# Boost-Shield-V1.net
KiCad netlist of a schematic drawn in Altium Designer
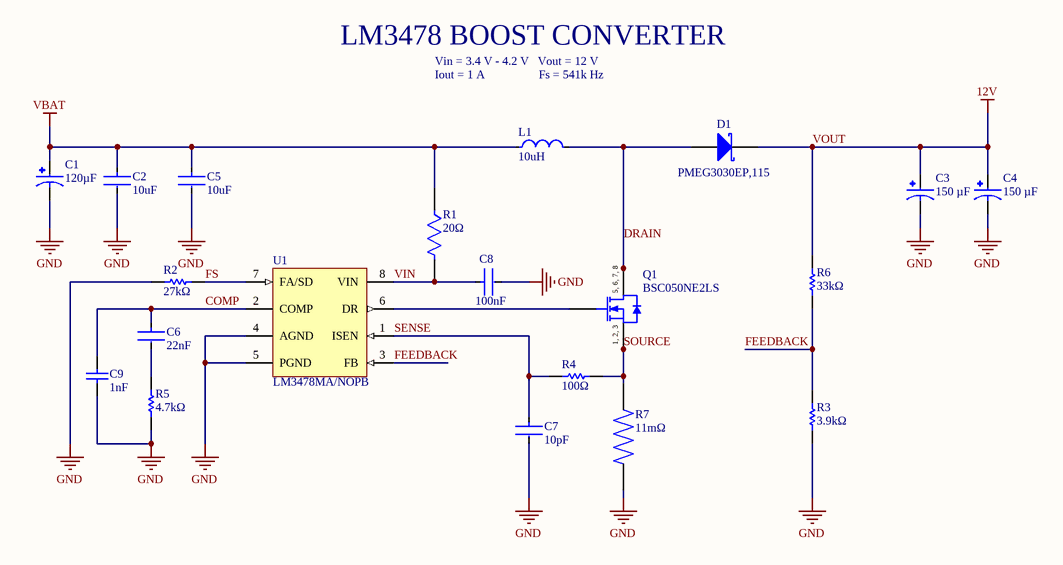
[diagram p0: Boost-Shield-V1.SchDoc]

(export (version "E")
  (design (tool "Eeschema 10.0.6"))
  (components
    (comp (ref "C1")
      (value "120µF")
      (footprint "CAP_EEFCX0J121R")
      (description "120µF 6.3V Aluminum - Polymer Capacitors 2917 (7343 Metric) 15mOhm 2000 Hrs @ 105°C  EEFCX0J121R")
      (libsource (lib "Boost-Shield") (part "EEFCX0J121R"))
    )
    (comp (ref "C2")
      (value "10uF")
      (footprint "FP-C0805C-DG-MFG")
      (description "CAP CER 10UF 10V X5R 0805")
      (fields (field (name "TOLERANCE") "10%") (field (name "MANUFACTURER PART NUMBER") "C0805C106K8PACTU"))
      (libsource (lib "Altium Content Vault") (part "11868f565c42a9108669ba33697ecf6"))
    )
    (comp (ref "C3")
      (value "150 µF")
      (footprint "CAP_16TDC150MYF")
      (description "150 µF Molded Tantalum Polymer Capacitor 16 V 2917 (7343 Metric) 50mOhm @ 100kHz")
      (libsource (lib "Boost-Shield") (part "16TDC150MYF"))
    )
    (comp (ref "C4")
      (value "150 µF")
      (footprint "CAP_16TDC150MYF")
      (description "150 µF Molded Tantalum Polymer Capacitor 16 V 2917 (7343 Metric) 50mOhm @ 100kHz")
      (libsource (lib "Boost-Shield") (part "16TDC150MYF"))
    )
    (comp (ref "C5")
      (value "10uF")
      (footprint "FP-C0805C-DG-MFG")
      (description "CAP CER 10UF 10V X5R 0805")
      (fields (field (name "TOLERANCE") "10%") (field (name "MANUFACTURER PART NUMBER") "C0805C106K8PACTU"))
      (libsource (lib "Altium Content Vault") (part "11868f565c42a9108669ba33697ecf6"))
    )
    (comp (ref "C6")
      (value "22nF")
      (footprint "FP-CGA4J-MFG")
      (description "Cap Ceramic 22nF 50V C0G 5% Pad SMD 0805 +125°C Automotive T/R CGJ4J2C0G1H223J125AA")
      (fields (field (name "TOLERANCE") "5%"))
      (libsource (lib "Altium Content Vault") (part "b4654b650e69147ec39a6b967a45e02"))
    )
    (comp (ref "C7")
      (value "10pF")
      (footprint "FP-C0805C-DN-MFG")
      (description "CAP CER 10PF 16V 20% NP0 0805")
      (fields
        (field (name "MANUFACTURER PART NUMBER") "C0805C100M4GACTU")
        (field (name "OCTOPART") "https://octopart.com/c0805c100m4gactu-kemet-16430157")
      )
      (libsource (lib "Altium Content Vault") (part "b4654b650e69147ec39a6b967a45e02"))
    )
    (comp (ref "C8")
      (value "100nF")
      (footprint "FP-CC0805-0_85-MFG")
      (description "CAP CER 0.1UF 16V X7R 0805")
      (fields
        (field (name "MANUFACTURER PART NUMBER") "CC0805KRX7R7BB104")
        (field (name "MANUFACTURER") "Yageo")
      )
      (libsource (lib "Altium Content Vault") (part "11868f565c42a9108669ba33697ecf6"))
    )
    (comp (ref "C9")
      (value "1nF")
      (footprint "CAPC2013X140X50NL20T25")
      (description "08051A102JAT2A")
      (fields (field (name "MANUFACTURER") "AVX Interconnect / Elco"))
      (libsource (lib "Altium Content Vault") (part "CAP"))
    )
    (comp (ref "D1")
      (value "PMEG3030EP,115")
      (footprint "NXP-SOD128_V")
      (description "Schottky Barrier Rectifier, 3 A, 30 V, -55 to 150 degC, 2-Pin SOD128, RoHS, Tape and Reel")
      (fields (field (name "MANUFACTURER") "NXP Semiconductors"))
      (libsource (lib "Altium Content Vault") (part "DSKY-AK-2"))
    )
    (comp (ref "L1")
      (value "10uH")
      (footprint "FP-IHLP-3232DZ-FP_2_413x5-MFG")
      (description "FIXED IND 10UH 5.2A 59.9 MOHM")
      (fields (field (name "TOLERANCE") "20%"))
      (libsource (lib "Altium Content Vault") (part "725321dda6339637d4d059423bc1c3c"))
    )
    (comp (ref "Q1")
      (value "BSC050NE2LS")
      (footprint "INF-PG-TDSON-8-1_V")
      (description "N-Channel OptiMOS Power-MOSFET, 25 V VDS, 58 A ID, -55 to 150 degC, PG-TDSON-8-1, Reel, Green")
      (fields (field (name "MANUFACTURER") "Infineon"))
      (libsource (lib "Altium Content Vault") (part "INF-NEMOS-SSSGDDDD-8"))
    )
    (comp (ref "R1")
      (value "20Ω")
      (footprint "FP-CRCW0805-e3-IPC_C")
      (description "RES Thick Film, 20Ω, 1%, 0.125W, 100ppm/°C, 0805")
      (fields (field (name "TOLERANCE") "1%"))
      (libsource (lib "Altium Content Vault") (part "1029c3af85768c4190bb7ad29bc67b5"))
    )
    (comp (ref "R2")
      (value "27kΩ")
      (footprint "RESC2013X50X30ML20T20")
      (description "CRCW080527K0FKEA")
      (fields (field (name "MANUFACTURER") "Vishay Dale"))
      (libsource (lib "Altium Content Vault") (part "RES"))
    )
    (comp (ref "R3")
      (value "3.9kΩ")
      (footprint "RESC2013X50X30LL20T20")
      (description "CRCW08053K90FKEA")
      (fields (field (name "MANUFACTURER") "Vishay Dale"))
      (libsource (lib "Altium Content Vault") (part "RES"))
    )
    (comp (ref "R4")
      (value "100Ω")
      (footprint "RESC2013X50X30ML20T20")
      (description "CRCW0805100RJNEA")
      (fields (field (name "MANUFACTURER") "Vishay Dale"))
      (libsource (lib "Altium Content Vault") (part "RES"))
    )
    (comp (ref "R5")
      (value "4.7kΩ")
      (footprint "RESC2013X70X40NL20T20")
      (description "Chip Resistor, 4.7 KOhm, +/- 1%, 0.125 W, -55 to 155 degC, 0805 (2012 Metric), RoHS, Tape and Reel")
      (fields (field (name "MANUFACTURER") "Panasonic"))
      (libsource (lib "Altium Content Vault") (part "RES-2"))
    )
    (comp (ref "R6")
      (value "33kΩ")
      (footprint "RESC2013X50X30LL20T20")
      (description "CRCW080533K0JNEA")
      (fields (field (name "MANUFACTURER") "Vishay Dale"))
      (libsource (lib "Altium Content Vault") (part "RES"))
    )
    (comp (ref "R7")
      (value "11mΩ")
      (footprint "RESC3115X65N")
      (description "11 mOhms ±1% 0.5W, 1/2W Chip Resistor 1206 (3216 Metric) Current Sense Thick Film")
      (libsource (lib "Boost-Shield") (part "RLP73V2BR011FTDF"))
    )
    (comp (ref "U1")
      (value "LM3478MA/NOPB")
      (footprint "D0008A_L")
      (fields (field (name "MANUFACTURER") "Texas Instruments"))
      (libsource (lib "Altium Content Vault") (part "PM-SWREG-LM3478-8"))
    )
  )
  (nets
    (net (code "1") (name "/COMP") (class "Default")
      (node (ref "C6") (pin "1") (pinfunction "1_1") (pintype "passive"))
      (node (ref "C9") (pin "2") (pinfunction "2_2") (pintype "passive"))
      (node (ref "U1") (pin "2") (pinfunction "COMP_2") (pintype "passive"))
    )
    (net (code "2") (name "/DRAIN") (class "Default")
      (node (ref "D1") (pin "1") (pinfunction "A_1") (pintype "passive"))
      (node (ref "L1") (pin "2") (pinfunction "2_2") (pintype "passive"))
      (node (ref "Q1") (pin "5") (pinfunction "DRAIN_5") (pintype "passive"))
      (node (ref "Q1") (pin "6") (pinfunction "DRAIN_6") (pintype "passive"))
      (node (ref "Q1") (pin "7") (pinfunction "DRAIN_7") (pintype "passive"))
      (node (ref "Q1") (pin "8") (pinfunction "DRAIN_8") (pintype "passive"))
    )
    (net (code "3") (name "/FEEDBACK") (class "Default")
      (node (ref "R3") (pin "2") (pinfunction "2_2") (pintype "passive"))
      (node (ref "R6") (pin "1") (pinfunction "1_1") (pintype "passive"))
      (node (ref "U1") (pin "3") (pinfunction "FB_3") (pintype "input"))
    )
    (net (code "4") (name "/FS") (class "Default")
      (node (ref "R2") (pin "2") (pinfunction "2_2") (pintype "passive"))
      (node (ref "U1") (pin "7") (pinfunction "FA/SD_7") (pintype "input"))
    )
    (net (code "5") (name "/SENSE") (class "Default")
      (node (ref "C7") (pin "1") (pinfunction "1_1") (pintype "passive"))
      (node (ref "R4") (pin "1") (pinfunction "1_1") (pintype "passive"))
      (node (ref "U1") (pin "1") (pinfunction "ISEN_1") (pintype "input"))
    )
    (net (code "6") (name "/SOURCE") (class "Default")
      (node (ref "Q1") (pin "1") (pinfunction "SOURCE_1") (pintype "passive"))
      (node (ref "Q1") (pin "2") (pinfunction "SOURCE_2") (pintype "passive"))
      (node (ref "Q1") (pin "3") (pinfunction "SOURCE_3") (pintype "passive"))
      (node (ref "R4") (pin "2") (pinfunction "2_2") (pintype "passive"))
      (node (ref "R7") (pin "2") (pinfunction "2_2") (pintype "passive"))
    )
    (net (code "7") (name "/VIN") (class "Default")
      (node (ref "C8") (pin "1") (pinfunction "1_1") (pintype "passive"))
      (node (ref "R1") (pin "2") (pinfunction "2_2") (pintype "passive"))
      (node (ref "U1") (pin "8") (pinfunction "VIN_8") (pintype "power_in"))
    )
    (net (code "8") (name "12V") (class "Default")
      (node (ref "C3") (pin "1") (pinfunction "1_1") (pintype "passive"))
      (node (ref "C4") (pin "1") (pinfunction "1_1") (pintype "passive"))
      (node (ref "D1") (pin "2") (pinfunction "K_2") (pintype "passive"))
      (node (ref "R6") (pin "2") (pinfunction "2_2") (pintype "passive"))
    )
    (net (code "9") (name "GND") (class "Default")
      (node (ref "C1") (pin "2") (pinfunction "2_2") (pintype "passive"))
      (node (ref "C2") (pin "2") (pinfunction "2_2") (pintype "passive"))
      (node (ref "C3") (pin "2") (pinfunction "2_2") (pintype "passive"))
      (node (ref "C4") (pin "2") (pinfunction "2_2") (pintype "passive"))
      (node (ref "C5") (pin "2") (pinfunction "2_2") (pintype "passive"))
      (node (ref "C7") (pin "2") (pinfunction "2_2") (pintype "passive"))
      (node (ref "C8") (pin "2") (pinfunction "2_2") (pintype "passive"))
      (node (ref "C9") (pin "1") (pinfunction "1_1") (pintype "passive"))
      (node (ref "R2") (pin "1") (pinfunction "1_1") (pintype "passive"))
      (node (ref "R3") (pin "1") (pinfunction "1_1") (pintype "passive"))
      (node (ref "R5") (pin "1") (pinfunction "1_1") (pintype "passive"))
      (node (ref "R7") (pin "1") (pinfunction "1_1") (pintype "passive"))
      (node (ref "U1") (pin "4") (pinfunction "AGND_4") (pintype "power_in"))
      (node (ref "U1") (pin "5") (pinfunction "PGND_5") (pintype "power_in"))
    )
    (net (code "10") (name "Net-(C6-Pad2)") (class "Default")
      (node (ref "C6") (pin "2") (pinfunction "2_2") (pintype "passive"))
      (node (ref "R5") (pin "2") (pinfunction "2_2") (pintype "passive"))
    )
    (net (code "11") (name "Net-(Q1-GATE)") (class "Default")
      (node (ref "Q1") (pin "4") (pinfunction "GATE_4") (pintype "passive"))
      (node (ref "U1") (pin "6") (pinfunction "DR_6") (pintype "output"))
    )
    (net (code "12") (name "VBAT") (class "Default")
      (node (ref "C1") (pin "1") (pinfunction "1_1") (pintype "passive"))
      (node (ref "C2") (pin "1") (pinfunction "1_1") (pintype "passive"))
      (node (ref "C5") (pin "1") (pinfunction "1_1") (pintype "passive"))
      (node (ref "L1") (pin "1") (pinfunction "1_1") (pintype "passive"))
      (node (ref "R1") (pin "1") (pinfunction "1_1") (pintype "passive"))
    )
  )
)
